# IoT_Switch-V1.net
KiCad netlist of a schematic drawn in EAGLE
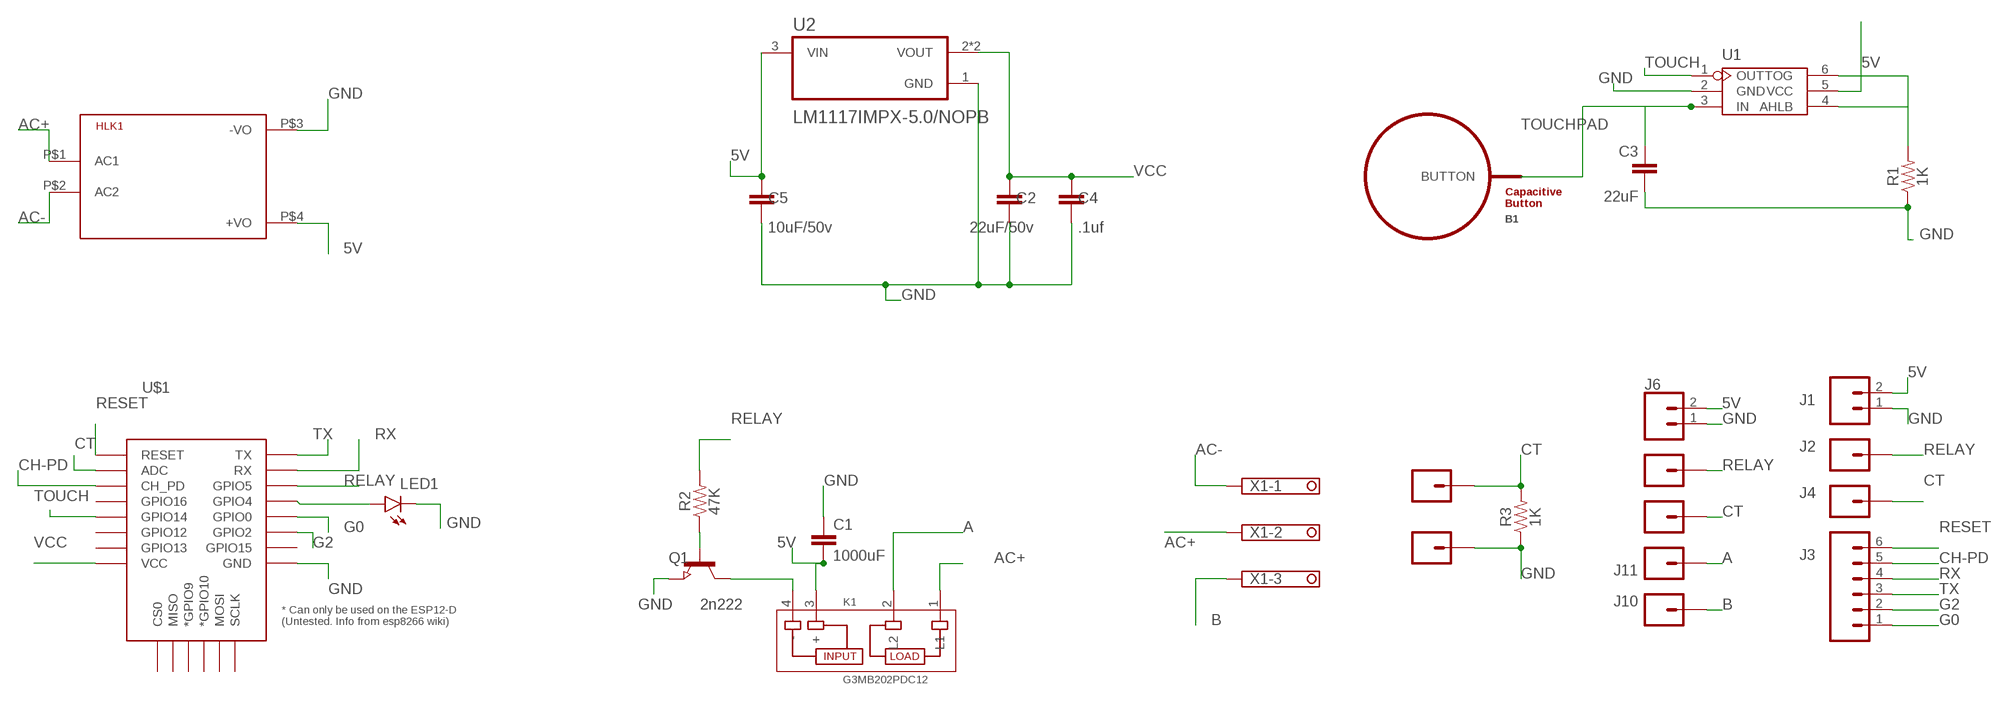
[diagram p0: schematic, sheet 1]

(export (version "E")
  (design (tool "Eeschema 10.0.6"))
  (components
    (comp (ref "B1")
      (value "BUTTON_PASSIVE8MM")
      (footprint "eagle-import:BUTTON_PASSIVE_8MM")
      (libsource (lib "eagle-import") (part "BUTTON_PASSIVE8MM"))
    )
    (comp (ref "C1")
      (value "1000uF")
      (footprint "eagle-import:0805")
      (libsource (lib "eagle-import") (part "1.0UF-0805-25V-10%"))
    )
    (comp (ref "C2")
      (value "22uF/50v")
      (footprint "eagle-import:0805")
      (libsource (lib "eagle-import") (part "22UF-0805-6.3V-20%"))
    )
    (comp (ref "C3")
      (value "22uF")
      (footprint "eagle-import:0805")
      (libsource (lib "eagle-import") (part "22UF-0805-6.3V-20%"))
    )
    (comp (ref "C4")
      (value ".1uf")
      (footprint "eagle-import:0805")
      (libsource (lib "eagle-import") (part "22UF-0805-6.3V-20%"))
    )
    (comp (ref "C5")
      (value "10uF/50v")
      (footprint "eagle-import:0805")
      (libsource (lib "eagle-import") (part "22UF-0805-6.3V-20%"))
    )
    (comp (ref "HLK1")
      (value "HLK-PM013W")
      (footprint "eagle-import:HLK-PM01")
      (libsource (lib "eagle-import") (part "HLK-PM013W"))
    )
    (comp (ref "J1")
      (value "CONN_02")
      (footprint "eagle-import:1X02")
      (libsource (lib "eagle-import") (part "CONN_02"))
    )
    (comp (ref "J2")
      (value "CONN_01")
      (footprint "eagle-import:1X01")
      (libsource (lib "eagle-import") (part "CONN_01"))
    )
    (comp (ref "J3")
      (value "CONN_06NO_SILK_FEMALE_PTH")
      (footprint "eagle-import:1X06_NO_SILK")
      (libsource (lib "eagle-import") (part "CONN_06NO_SILK_FEMALE_PTH"))
    )
    (comp (ref "J4")
      (value "CONN_01")
      (footprint "eagle-import:1X01")
      (libsource (lib "eagle-import") (part "CONN_01"))
    )
    (comp (ref "J5")
      (value "CONN_01")
      (footprint "eagle-import:1X01")
      (libsource (lib "eagle-import") (part "CONN_01"))
    )
    (comp (ref "J6")
      (value "CONN_02")
      (footprint "eagle-import:1X02")
      (libsource (lib "eagle-import") (part "CONN_02"))
    )
    (comp (ref "J7")
      (value "CONN_01")
      (footprint "eagle-import:1X01")
      (libsource (lib "eagle-import") (part "CONN_01"))
    )
    (comp (ref "J8")
      (value "CONN_01")
      (footprint "eagle-import:1X01")
      (libsource (lib "eagle-import") (part "CONN_01"))
    )
    (comp (ref "J9")
      (value "CONN_01")
      (footprint "eagle-import:1X01")
      (libsource (lib "eagle-import") (part "CONN_01"))
    )
    (comp (ref "J10")
      (value "CONN_01")
      (footprint "eagle-import:1X01")
      (libsource (lib "eagle-import") (part "CONN_01"))
    )
    (comp (ref "J11")
      (value "CONN_01")
      (footprint "eagle-import:1X01")
      (libsource (lib "eagle-import") (part "CONN_01"))
    )
    (comp (ref "K1")
      (value "G3MB202PDC12")
      (footprint "eagle-import:RELAY_G3MB202PDC12")
      (fields (field (name "MF") "Omron Automation") (field (name "MP") "G3MB-202P-DC12"))
      (libsource (lib "eagle-import") (part "G3MB202PDC12"))
    )
    (comp (ref "LED1")
      (value "LED1206")
      (footprint "eagle-import:LED-1206")
      (libsource (lib "eagle-import") (part "LED1206"))
    )
    (comp (ref "Q1")
      (value "2n222")
      (footprint "eagle-import:SOT23")
      (libsource (lib "eagle-import") (part "NPN-TRANSISTOR_SOT23"))
    )
    (comp (ref "R1")
      (value "1K")
      (footprint "eagle-import:0805")
      (libsource (lib "eagle-import") (part "RESISTOR0805"))
    )
    (comp (ref "R2")
      (value "47K")
      (footprint "eagle-import:0805")
      (libsource (lib "eagle-import") (part "RESISTOR0805"))
    )
    (comp (ref "R3")
      (value "1K")
      (footprint "eagle-import:0805")
      (libsource (lib "eagle-import") (part "RESISTOR0805"))
    )
    (comp (ref "U$1")
      (value "ESP12ESMD")
      (footprint "eagle-import:ESP12E-SMD")
      (libsource (lib "eagle-import") (part "ESP12ESMD"))
    )
    (comp (ref "U1")
      (value "TTP223")
      (footprint "eagle-import:SOT23-6L")
      (fields (field (name "MF") "TONTEK") (field (name "MP") "TTP223 "))
      (libsource (lib "eagle-import") (part "TTP223"))
    )
    (comp (ref "U2")
      (value "LM1117IMPX-5.0/NOPB")
      (footprint "eagle-import:SOT230P700X180-4N")
      (fields (field (name "MF") "Texas Instruments") (field (name "MP") "LM1117IMPX-5.0"))
      (libsource (lib "eagle-import") (part "LM1117IMPX-5.0/NOPB"))
    )
    (comp (ref "X1")
      (value "TERMINAL-BLOCK-3.5MM-3-PIN-ROUND-PAD")
      (footprint "eagle-import:TERMINAL-BLOCK-3-PIN-3.5MM-ROUND-PAD")
      (libsource (lib "eagle-import") (part "TERMINAL-BLOCK-3.5MM-3-PIN-ROUND-PAD"))
    )
  )
  (nets
    (net (code "1") (name "/5V") (class "Default")
      (node (ref "C1") (pin "2") (pinfunction "2_2") (pintype "passive"))
      (node (ref "C5") (pin "1") (pinfunction "1_1") (pintype "passive"))
      (node (ref "HLK1") (pin "P$4") (pinfunction "+VO_P$4") (pintype "bidirectional"))
      (node (ref "J1") (pin "2") (pinfunction "2_2") (pintype "passive"))
      (node (ref "J6") (pin "2") (pinfunction "2_2") (pintype "passive"))
      (node (ref "K1") (pin "3") (pinfunction "+_3") (pintype "power_in"))
      (node (ref "U1") (pin "5") (pinfunction "VCC_5") (pintype "bidirectional"))
      (node (ref "U2") (pin "3") (pinfunction "VIN_3") (pintype "input"))
    )
    (net (code "2") (name "/A") (class "Default")
      (node (ref "J11") (pin "1") (pinfunction "1_1") (pintype "passive"))
      (node (ref "K1") (pin "2") (pinfunction "L2_2") (pintype "power_in"))
    )
    (net (code "3") (name "/AC+") (class "Default")
      (node (ref "HLK1") (pin "P$1") (pinfunction "AC1_P$1") (pintype "bidirectional"))
      (node (ref "K1") (pin "1") (pinfunction "L1_1") (pintype "power_in"))
      (node (ref "X1") (pin "2") (pinfunction "K_2") (pintype "passive"))
    )
    (net (code "4") (name "/AC-") (class "Default")
      (node (ref "HLK1") (pin "P$2") (pinfunction "AC2_P$2") (pintype "bidirectional"))
      (node (ref "X1") (pin "1") (pinfunction "K_1") (pintype "passive"))
    )
    (net (code "5") (name "/B") (class "Default")
      (node (ref "J10") (pin "1") (pinfunction "1_1") (pintype "passive"))
      (node (ref "X1") (pin "3") (pinfunction "K_3") (pintype "passive"))
    )
    (net (code "6") (name "/CH-PD") (class "Default")
      (node (ref "J3") (pin "5") (pinfunction "5_5") (pintype "passive"))
      (node (ref "U$1") (pin "CH_PD") (pinfunction "CH_PD_CH_PD") (pintype "bidirectional"))
    )
    (net (code "7") (name "/CT") (class "Default")
      (node (ref "J4") (pin "1") (pinfunction "1_1") (pintype "passive"))
      (node (ref "J7") (pin "1") (pinfunction "1_1") (pintype "passive"))
      (node (ref "J8") (pin "1") (pinfunction "1_1") (pintype "passive"))
      (node (ref "R3") (pin "2") (pinfunction "2_2") (pintype "passive"))
      (node (ref "U$1") (pin "ADC") (pinfunction "ADC_ADC") (pintype "bidirectional"))
    )
    (net (code "8") (name "/G0") (class "Default")
      (node (ref "J3") (pin "1") (pinfunction "1_1") (pintype "passive"))
      (node (ref "U$1") (pin "GPIO0") (pinfunction "GPIO0_GPIO0") (pintype "bidirectional"))
    )
    (net (code "9") (name "/G2") (class "Default")
      (node (ref "J3") (pin "2") (pinfunction "2_2") (pintype "passive"))
      (node (ref "U$1") (pin "GPIO2") (pinfunction "GPIO2_GPIO2") (pintype "bidirectional"))
    )
    (net (code "10") (name "/GND") (class "Default")
      (node (ref "C1") (pin "1") (pinfunction "1_1") (pintype "passive"))
      (node (ref "C2") (pin "2") (pinfunction "2_2") (pintype "passive"))
      (node (ref "C3") (pin "2") (pinfunction "2_2") (pintype "passive"))
      (node (ref "C4") (pin "2") (pinfunction "2_2") (pintype "passive"))
      (node (ref "C5") (pin "2") (pinfunction "2_2") (pintype "passive"))
      (node (ref "HLK1") (pin "P$3") (pinfunction "-VO_P$3") (pintype "bidirectional"))
      (node (ref "J1") (pin "1") (pinfunction "1_1") (pintype "passive"))
      (node (ref "J6") (pin "1") (pinfunction "1_1") (pintype "passive"))
      (node (ref "J9") (pin "1") (pinfunction "1_1") (pintype "passive"))
      (node (ref "LED1") (pin "C") (pinfunction "C_C") (pintype "passive"))
      (node (ref "Q1") (pin "2") (pinfunction "E_2") (pintype "passive"))
      (node (ref "R1") (pin "1") (pinfunction "1_1") (pintype "passive"))
      (node (ref "R3") (pin "1") (pinfunction "1_1") (pintype "passive"))
      (node (ref "U$1") (pin "GND") (pinfunction "GND_GND") (pintype "bidirectional"))
      (node (ref "U1") (pin "2") (pinfunction "GND_2") (pintype "bidirectional"))
      (node (ref "U2") (pin "1") (pinfunction "GND_1") (pintype "power_in"))
    )
    (net (code "11") (name "/RELAY") (class "Default")
      (node (ref "J2") (pin "1") (pinfunction "1_1") (pintype "passive"))
      (node (ref "J5") (pin "1") (pinfunction "1_1") (pintype "passive"))
      (node (ref "R2") (pin "2") (pinfunction "2_2") (pintype "passive"))
      (node (ref "U$1") (pin "GPIO5") (pinfunction "GPIO5_GPIO5") (pintype "bidirectional"))
    )
    (net (code "12") (name "/RESET") (class "Default")
      (node (ref "J3") (pin "6") (pinfunction "6_6") (pintype "passive"))
      (node (ref "U$1") (pin "RESET") (pinfunction "RESET_RESET") (pintype "bidirectional"))
    )
    (net (code "13") (name "/RX") (class "Default")
      (node (ref "J3") (pin "4") (pinfunction "4_4") (pintype "passive"))
      (node (ref "U$1") (pin "RXD0") (pinfunction "RX_RXD0") (pintype "bidirectional"))
    )
    (net (code "14") (name "/TOUCH") (class "Default")
      (node (ref "U$1") (pin "GPIO14") (pinfunction "GPIO14_GPIO14") (pintype "bidirectional"))
      (node (ref "U1") (pin "1") (pinfunction "OUT_1") (pintype "bidirectional"))
    )
    (net (code "15") (name "/TOUCHPAD") (class "Default")
      (node (ref "B1") (pin "BUTTON") (pinfunction "BUTTON_BUTTON") (pintype "passive"))
      (node (ref "C3") (pin "1") (pinfunction "1_1") (pintype "passive"))
      (node (ref "U1") (pin "3") (pinfunction "IN_3") (pintype "bidirectional"))
    )
    (net (code "16") (name "/TX") (class "Default")
      (node (ref "J3") (pin "3") (pinfunction "3_3") (pintype "passive"))
      (node (ref "U$1") (pin "TXD0") (pinfunction "TX_TXD0") (pintype "bidirectional"))
    )
    (net (code "17") (name "/VCC") (class "Default")
      (node (ref "C2") (pin "1") (pinfunction "1_1") (pintype "passive"))
      (node (ref "C4") (pin "1") (pinfunction "1_1") (pintype "passive"))
      (node (ref "U$1") (pin "VCC") (pinfunction "VCC_VCC") (pintype "bidirectional"))
      (node (ref "U2") (pin "2") (pinfunction "VOUT_2") (pintype "output"))
      (node (ref "U2") (pin "4") (pinfunction "VOUT_4") (pintype "output"))
    )
    (net (code "18") (name "Net-(K1--)") (class "Default")
      (node (ref "K1") (pin "4") (pinfunction "-_4") (pintype "power_in"))
      (node (ref "Q1") (pin "3") (pinfunction "C_3") (pintype "passive"))
    )
    (net (code "19") (name "Net-(LED1-PadA)") (class "Default")
      (node (ref "LED1") (pin "A") (pinfunction "A_A") (pintype "passive"))
      (node (ref "U$1") (pin "GPIO4") (pinfunction "GPIO4_GPIO4") (pintype "bidirectional"))
    )
    (net (code "20") (name "Net-(Q1-B)") (class "Default")
      (node (ref "Q1") (pin "1") (pinfunction "B_1") (pintype "passive"))
      (node (ref "R2") (pin "1") (pinfunction "1_1") (pintype "passive"))
    )
    (net (code "21") (name "Net-(U1-AHLB)") (class "Default")
      (node (ref "R1") (pin "2") (pinfunction "2_2") (pintype "passive"))
      (node (ref "U1") (pin "4") (pinfunction "AHLB_4") (pintype "bidirectional"))
      (node (ref "U1") (pin "6") (pinfunction "TOG_6") (pintype "bidirectional"))
    )
    (net (code "22") (name "unconnected-(U$1-*GPIO9-PadGPIO9)") (class "Default")
      (node (ref "U$1") (pin "GPIO9") (pinfunction "*GPIO9_GPIO9") (pintype "bidirectional"))
    )
    (net (code "23") (name "unconnected-(U$1-*GPIO10-PadGPIO10)") (class "Default")
      (node (ref "U$1") (pin "GPIO10") (pinfunction "*GPIO10_GPIO10") (pintype "bidirectional"))
    )
    (net (code "24") (name "unconnected-(U$1-PadCS0)") (class "Default")
      (node (ref "U$1") (pin "CS0") (pinfunction "CS0_CS0") (pintype "bidirectional"))
    )
    (net (code "25") (name "unconnected-(U$1-PadGPIO12)") (class "Default")
      (node (ref "U$1") (pin "GPIO12") (pinfunction "GPIO12_GPIO12") (pintype "bidirectional"))
    )
    (net (code "26") (name "unconnected-(U$1-PadGPIO13)") (class "Default")
      (node (ref "U$1") (pin "GPIO13") (pinfunction "GPIO13_GPIO13") (pintype "bidirectional"))
    )
    (net (code "27") (name "unconnected-(U$1-PadGPIO15)") (class "Default")
      (node (ref "U$1") (pin "GPIO15") (pinfunction "GPIO15_GPIO15") (pintype "bidirectional"))
    )
    (net (code "28") (name "unconnected-(U$1-PadGPIO16)") (class "Default")
      (node (ref "U$1") (pin "GPIO16") (pinfunction "GPIO16_GPIO16") (pintype "bidirectional"))
    )
    (net (code "29") (name "unconnected-(U$1-PadMISO)") (class "Default")
      (node (ref "U$1") (pin "MISO") (pinfunction "MISO_MISO") (pintype "bidirectional"))
    )
    (net (code "30") (name "unconnected-(U$1-PadMOSI)") (class "Default")
      (node (ref "U$1") (pin "MOSI") (pinfunction "MOSI_MOSI") (pintype "bidirectional"))
    )
    (net (code "31") (name "unconnected-(U$1-PadSCLK)") (class "Default")
      (node (ref "U$1") (pin "SCLK") (pinfunction "SCLK_SCLK") (pintype "bidirectional"))
    )
  )
)
